# SDRAM.net
KiCad netlist of a schematic drawn in Altium Designer
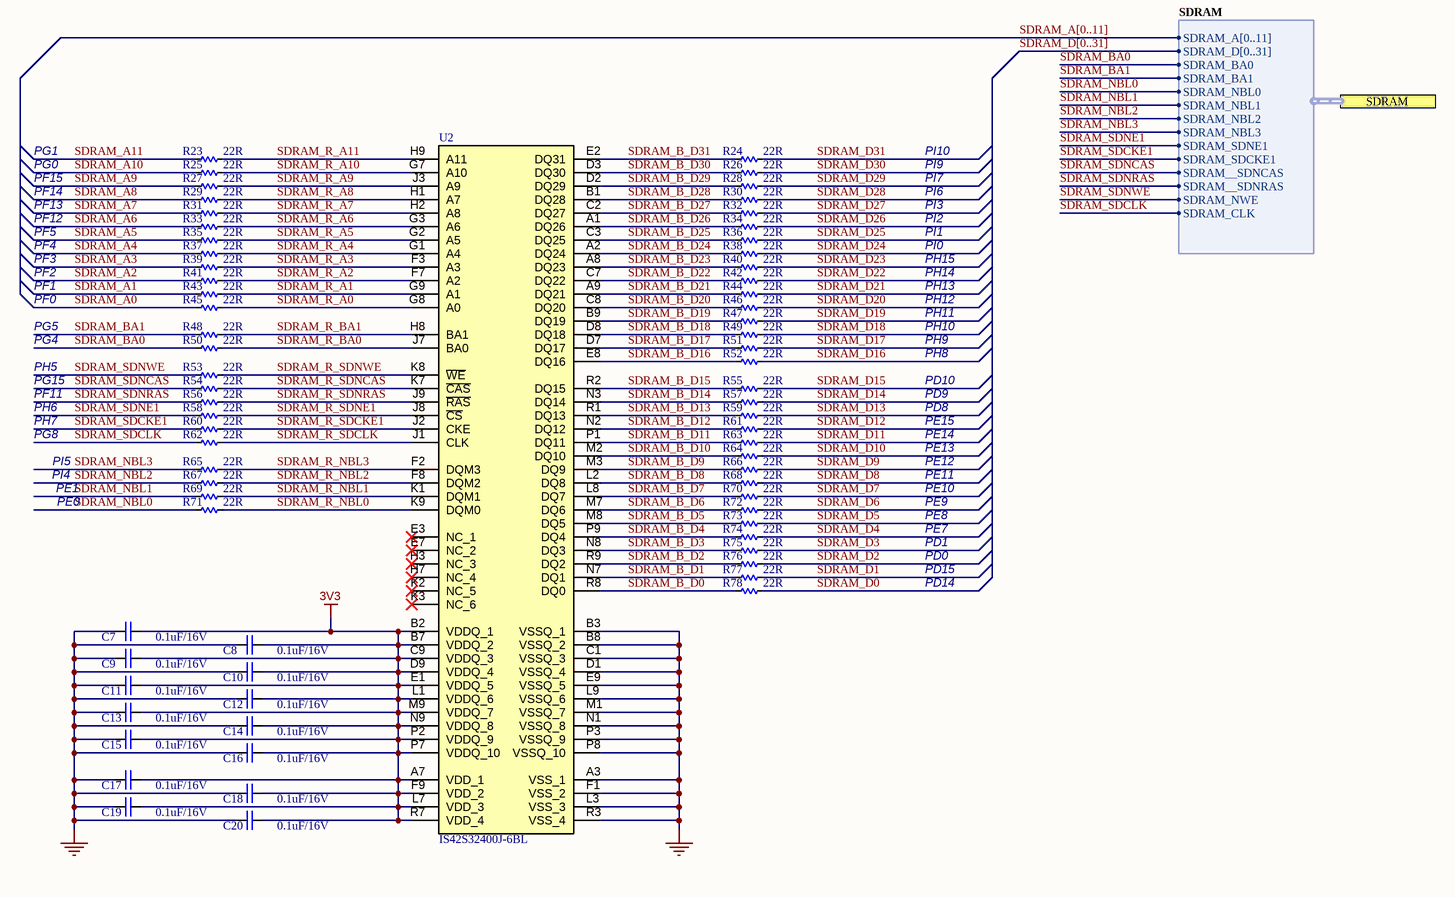
[diagram p0: SDRAM.SchDoc]

(export (version "E")
  (design (tool "Eeschema 10.0.6"))
  (components
    (comp (ref "C7")
      (value "0.1uF/16V")
      (footprint "CAP_C_1608X80")
      (description "CAP_Chip")
      (libsource (lib "LABLIB") (part "CAP_SMD"))
    )
    (comp (ref "C8")
      (value "0.1uF/16V")
      (footprint "CAP_C_1608X80")
      (description "CAP_Chip")
      (libsource (lib "LABLIB") (part "CAP_SMD"))
    )
    (comp (ref "C9")
      (value "0.1uF/16V")
      (footprint "CAP_C_1608X80")
      (description "CAP_Chip")
      (libsource (lib "LABLIB") (part "CAP_SMD"))
    )
    (comp (ref "C10")
      (value "0.1uF/16V")
      (footprint "CAP_C_1608X80")
      (description "CAP_Chip")
      (libsource (lib "LABLIB") (part "CAP_SMD"))
    )
    (comp (ref "C11")
      (value "0.1uF/16V")
      (footprint "CAP_C_1608X80")
      (description "CAP_Chip")
      (libsource (lib "LABLIB") (part "CAP_SMD"))
    )
    (comp (ref "C12")
      (value "0.1uF/16V")
      (footprint "CAP_C_1608X80")
      (description "CAP_Chip")
      (libsource (lib "LABLIB") (part "CAP_SMD"))
    )
    (comp (ref "C13")
      (value "0.1uF/16V")
      (footprint "CAP_C_1608X80")
      (description "CAP_Chip")
      (libsource (lib "LABLIB") (part "CAP_SMD"))
    )
    (comp (ref "C14")
      (value "0.1uF/16V")
      (footprint "CAP_C_1608X80")
      (description "CAP_Chip")
      (libsource (lib "LABLIB") (part "CAP_SMD"))
    )
    (comp (ref "C15")
      (value "0.1uF/16V")
      (footprint "CAP_C_1608X80")
      (description "CAP_Chip")
      (libsource (lib "LABLIB") (part "CAP_SMD"))
    )
    (comp (ref "C16")
      (value "0.1uF/16V")
      (footprint "CAP_C_1608X80")
      (description "CAP_Chip")
      (libsource (lib "LABLIB") (part "CAP_SMD"))
    )
    (comp (ref "C17")
      (value "0.1uF/16V")
      (footprint "CAP_C_1608X80")
      (description "CAP_Chip")
      (libsource (lib "LABLIB") (part "CAP_SMD"))
    )
    (comp (ref "C18")
      (value "0.1uF/16V")
      (footprint "CAP_C_1608X80")
      (description "CAP_Chip")
      (libsource (lib "LABLIB") (part "CAP_SMD"))
    )
    (comp (ref "C19")
      (value "0.1uF/16V")
      (footprint "CAP_C_1608X80")
      (description "CAP_Chip")
      (libsource (lib "LABLIB") (part "CAP_SMD"))
    )
    (comp (ref "C20")
      (value "0.1uF/16V")
      (footprint "CAP_C_1608X80")
      (description "CAP_Chip")
      (libsource (lib "LABLIB") (part "CAP_SMD"))
    )
    (comp (ref "R23")
      (value "22R")
      (footprint "RES_C_1608X60")
      (description "RES")
      (libsource (lib "LABLIB") (part "_RES_B_2"))
    )
    (comp (ref "R24")
      (value "22R")
      (footprint "RES_C_1608X60")
      (description "RES")
      (libsource (lib "LABLIB") (part "_RES_B_2"))
    )
    (comp (ref "R25")
      (value "22R")
      (footprint "RES_C_1608X60")
      (description "RES")
      (libsource (lib "LABLIB") (part "_RES_B_2"))
    )
    (comp (ref "R26")
      (value "22R")
      (footprint "RES_C_1608X60")
      (description "RES")
      (libsource (lib "LABLIB") (part "_RES_B_2"))
    )
    (comp (ref "R27")
      (value "22R")
      (footprint "RES_C_1608X60")
      (description "RES")
      (libsource (lib "LABLIB") (part "_RES_B_2"))
    )
    (comp (ref "R28")
      (value "22R")
      (footprint "RES_C_1608X60")
      (description "RES")
      (libsource (lib "LABLIB") (part "_RES_B_2"))
    )
    (comp (ref "R29")
      (value "22R")
      (footprint "RES_C_1608X60")
      (description "RES")
      (libsource (lib "LABLIB") (part "_RES_B_2"))
    )
    (comp (ref "R30")
      (value "22R")
      (footprint "RES_C_1608X60")
      (description "RES")
      (libsource (lib "LABLIB") (part "_RES_B_2"))
    )
    (comp (ref "R31")
      (value "22R")
      (footprint "RES_C_1608X60")
      (description "RES")
      (libsource (lib "LABLIB") (part "_RES_B_2"))
    )
    (comp (ref "R32")
      (value "22R")
      (footprint "RES_C_1608X60")
      (description "RES")
      (libsource (lib "LABLIB") (part "_RES_B_2"))
    )
    (comp (ref "R33")
      (value "22R")
      (footprint "RES_C_1608X60")
      (description "RES")
      (libsource (lib "LABLIB") (part "_RES_B_2"))
    )
    (comp (ref "R34")
      (value "22R")
      (footprint "RES_C_1608X60")
      (description "RES")
      (libsource (lib "LABLIB") (part "_RES_B_2"))
    )
    (comp (ref "R35")
      (value "22R")
      (footprint "RES_C_1608X60")
      (description "RES")
      (libsource (lib "LABLIB") (part "_RES_B_2"))
    )
    (comp (ref "R36")
      (value "22R")
      (footprint "RES_C_1608X60")
      (description "RES")
      (libsource (lib "LABLIB") (part "_RES_B_2"))
    )
    (comp (ref "R37")
      (value "22R")
      (footprint "RES_C_1608X60")
      (description "RES")
      (libsource (lib "LABLIB") (part "_RES_B_2"))
    )
    (comp (ref "R38")
      (value "22R")
      (footprint "RES_C_1608X60")
      (description "RES")
      (libsource (lib "LABLIB") (part "_RES_B_2"))
    )
    (comp (ref "R39")
      (value "22R")
      (footprint "RES_C_1608X60")
      (description "RES")
      (libsource (lib "LABLIB") (part "_RES_B_2"))
    )
    (comp (ref "R40")
      (value "22R")
      (footprint "RES_C_1608X60")
      (description "RES")
      (libsource (lib "LABLIB") (part "_RES_B_2"))
    )
    (comp (ref "R41")
      (value "22R")
      (footprint "RES_C_1608X60")
      (description "RES")
      (libsource (lib "LABLIB") (part "_RES_B_2"))
    )
    (comp (ref "R42")
      (value "22R")
      (footprint "RES_C_1608X60")
      (description "RES")
      (libsource (lib "LABLIB") (part "_RES_B_2"))
    )
    (comp (ref "R43")
      (value "22R")
      (footprint "RES_C_1608X60")
      (description "RES")
      (libsource (lib "LABLIB") (part "_RES_B_2"))
    )
    (comp (ref "R44")
      (value "22R")
      (footprint "RES_C_1608X60")
      (description "RES")
      (libsource (lib "LABLIB") (part "_RES_B_2"))
    )
    (comp (ref "R45")
      (value "22R")
      (footprint "RES_C_1608X60")
      (description "RES")
      (libsource (lib "LABLIB") (part "_RES_B_2"))
    )
    (comp (ref "R46")
      (value "22R")
      (footprint "RES_C_1608X60")
      (description "RES")
      (libsource (lib "LABLIB") (part "_RES_B_2"))
    )
    (comp (ref "R47")
      (value "22R")
      (footprint "RES_C_1608X60")
      (description "RES")
      (libsource (lib "LABLIB") (part "_RES_B_2"))
    )
    (comp (ref "R48")
      (value "22R")
      (footprint "RES_C_1608X60")
      (description "RES")
      (libsource (lib "LABLIB") (part "_RES_B_2"))
    )
    (comp (ref "R49")
      (value "22R")
      (footprint "RES_C_1608X60")
      (description "RES")
      (libsource (lib "LABLIB") (part "_RES_B_2"))
    )
    (comp (ref "R50")
      (value "22R")
      (footprint "RES_C_1608X60")
      (description "RES")
      (libsource (lib "LABLIB") (part "_RES_B_2"))
    )
    (comp (ref "R51")
      (value "22R")
      (footprint "RES_C_1608X60")
      (description "RES")
      (libsource (lib "LABLIB") (part "_RES_B_2"))
    )
    (comp (ref "R52")
      (value "22R")
      (footprint "RES_C_1608X60")
      (description "RES")
      (libsource (lib "LABLIB") (part "_RES_B_2"))
    )
    (comp (ref "R53")
      (value "22R")
      (footprint "RES_C_1608X60")
      (description "RES")
      (libsource (lib "LABLIB") (part "_RES_B_2"))
    )
    (comp (ref "R54")
      (value "22R")
      (footprint "RES_C_1608X60")
      (description "RES")
      (libsource (lib "LABLIB") (part "_RES_B_2"))
    )
    (comp (ref "R55")
      (value "22R")
      (footprint "RES_C_1608X60")
      (description "RES")
      (libsource (lib "LABLIB") (part "_RES_B_2"))
    )
    (comp (ref "R56")
      (value "22R")
      (footprint "RES_C_1608X60")
      (description "RES")
      (libsource (lib "LABLIB") (part "_RES_B_2"))
    )
    (comp (ref "R57")
      (value "22R")
      (footprint "RES_C_1608X60")
      (description "RES")
      (libsource (lib "LABLIB") (part "_RES_B_2"))
    )
    (comp (ref "R58")
      (value "22R")
      (footprint "RES_C_1608X60")
      (description "RES")
      (libsource (lib "LABLIB") (part "_RES_B_2"))
    )
    (comp (ref "R59")
      (value "22R")
      (footprint "RES_C_1608X60")
      (description "RES")
      (libsource (lib "LABLIB") (part "_RES_B_2"))
    )
    (comp (ref "R60")
      (value "22R")
      (footprint "RES_C_1608X60")
      (description "RES")
      (libsource (lib "LABLIB") (part "_RES_B_2"))
    )
    (comp (ref "R61")
      (value "22R")
      (footprint "RES_C_1608X60")
      (description "RES")
      (libsource (lib "LABLIB") (part "_RES_B_2"))
    )
    (comp (ref "R62")
      (value "22R")
      (footprint "RES_C_1608X60")
      (description "RES")
      (libsource (lib "LABLIB") (part "_RES_B_2"))
    )
    (comp (ref "R63")
      (value "22R")
      (footprint "RES_C_1608X60")
      (description "RES")
      (libsource (lib "LABLIB") (part "_RES_B_2"))
    )
    (comp (ref "R64")
      (value "22R")
      (footprint "RES_C_1608X60")
      (description "RES")
      (libsource (lib "LABLIB") (part "_RES_B_2"))
    )
    (comp (ref "R65")
      (value "22R")
      (footprint "RES_C_1608X60")
      (description "RES")
      (libsource (lib "LABLIB") (part "_RES_B_2"))
    )
    (comp (ref "R66")
      (value "22R")
      (footprint "RES_C_1608X60")
      (description "RES")
      (libsource (lib "LABLIB") (part "_RES_B_2"))
    )
    (comp (ref "R67")
      (value "22R")
      (footprint "RES_C_1608X60")
      (description "RES")
      (libsource (lib "LABLIB") (part "_RES_B_2"))
    )
    (comp (ref "R68")
      (value "22R")
      (footprint "RES_C_1608X60")
      (description "RES")
      (libsource (lib "LABLIB") (part "_RES_B_2"))
    )
    (comp (ref "R69")
      (value "22R")
      (footprint "RES_C_1608X60")
      (description "RES")
      (libsource (lib "LABLIB") (part "_RES_B_2"))
    )
    (comp (ref "R70")
      (value "22R")
      (footprint "RES_C_1608X60")
      (description "RES")
      (libsource (lib "LABLIB") (part "_RES_B_2"))
    )
    (comp (ref "R71")
      (value "22R")
      (footprint "RES_C_1608X60")
      (description "RES")
      (libsource (lib "LABLIB") (part "_RES_B_2"))
    )
    (comp (ref "R72")
      (value "22R")
      (footprint "RES_C_1608X60")
      (description "RES")
      (libsource (lib "LABLIB") (part "_RES_B_2"))
    )
    (comp (ref "R73")
      (value "22R")
      (footprint "RES_C_1608X60")
      (description "RES")
      (libsource (lib "LABLIB") (part "_RES_B_2"))
    )
    (comp (ref "R74")
      (value "22R")
      (footprint "RES_C_1608X60")
      (description "RES")
      (libsource (lib "LABLIB") (part "_RES_B_2"))
    )
    (comp (ref "R75")
      (value "22R")
      (footprint "RES_C_1608X60")
      (description "RES")
      (libsource (lib "LABLIB") (part "_RES_B_2"))
    )
    (comp (ref "R76")
      (value "22R")
      (footprint "RES_C_1608X60")
      (description "RES")
      (libsource (lib "LABLIB") (part "_RES_B_2"))
    )
    (comp (ref "R77")
      (value "22R")
      (footprint "RES_C_1608X60")
      (description "RES")
      (libsource (lib "LABLIB") (part "_RES_B_2"))
    )
    (comp (ref "R78")
      (value "22R")
      (footprint "RES_C_1608X60")
      (description "RES")
      (libsource (lib "LABLIB") (part "_RES_B_2"))
    )
    (comp (ref "U2")
      (value "IS42S32400J-6BL")
      (footprint "BGA90C80P9X15_800X1300X120")
      (description "DRAM 128M, 3.3V, SDRAM, 4Mx32, 166Mhz, 90 ball BGA (8mmx13mm) RoHS")
      (libsource (lib "COMM_SCHLIB") (part "IS42S32400J-6BL"))
    )
  )
  (nets
    (net (code "2") (name "/SDRAM_A0") (class "Default")
      (node (ref "R45") (pin "1") (pinfunction "1_1") (pintype "passive"))
    )
    (net (code "3") (name "/SDRAM_A1") (class "Default")
      (node (ref "R43") (pin "1") (pinfunction "1_1") (pintype "passive"))
    )
    (net (code "4") (name "/SDRAM_A2") (class "Default")
      (node (ref "R41") (pin "1") (pinfunction "1_1") (pintype "passive"))
    )
    (net (code "5") (name "/SDRAM_A3") (class "Default")
      (node (ref "R39") (pin "1") (pinfunction "1_1") (pintype "passive"))
    )
    (net (code "6") (name "/SDRAM_A4") (class "Default")
      (node (ref "R37") (pin "1") (pinfunction "1_1") (pintype "passive"))
    )
    (net (code "7") (name "/SDRAM_A5") (class "Default")
      (node (ref "R35") (pin "1") (pinfunction "1_1") (pintype "passive"))
    )
    (net (code "8") (name "/SDRAM_A6") (class "Default")
      (node (ref "R33") (pin "1") (pinfunction "1_1") (pintype "passive"))
    )
    (net (code "9") (name "/SDRAM_A7") (class "Default")
      (node (ref "R31") (pin "1") (pinfunction "1_1") (pintype "passive"))
    )
    (net (code "10") (name "/SDRAM_A8") (class "Default")
      (node (ref "R29") (pin "1") (pinfunction "1_1") (pintype "passive"))
    )
    (net (code "11") (name "/SDRAM_A9") (class "Default")
      (node (ref "R27") (pin "1") (pinfunction "1_1") (pintype "passive"))
    )
    (net (code "12") (name "/SDRAM_A10") (class "Default")
      (node (ref "R25") (pin "1") (pinfunction "1_1") (pintype "passive"))
    )
    (net (code "13") (name "/SDRAM_A11") (class "Default")
      (node (ref "R23") (pin "1") (pinfunction "1_1") (pintype "passive"))
    )
    (net (code "15") (name "/SDRAM_BA0") (class "Default")
      (node (ref "R50") (pin "1") (pinfunction "1_1") (pintype "passive"))
    )
    (net (code "16") (name "/SDRAM_BA1") (class "Default")
      (node (ref "R48") (pin "1") (pinfunction "1_1") (pintype "passive"))
    )
    (net (code "17") (name "/SDRAM_B_D0") (class "Default")
      (node (ref "R78") (pin "1") (pinfunction "1_1") (pintype "passive"))
      (node (ref "U2") (pin "R8") (pinfunction "DQ0_R8") (pintype "passive"))
    )
    (net (code "18") (name "/SDRAM_B_D1") (class "Default")
      (node (ref "R77") (pin "1") (pinfunction "1_1") (pintype "passive"))
      (node (ref "U2") (pin "N7") (pinfunction "DQ1_N7") (pintype "passive"))
    )
    (net (code "19") (name "/SDRAM_B_D2") (class "Default")
      (node (ref "R76") (pin "1") (pinfunction "1_1") (pintype "passive"))
      (node (ref "U2") (pin "R9") (pinfunction "DQ2_R9") (pintype "passive"))
    )
    (net (code "20") (name "/SDRAM_B_D3") (class "Default")
      (node (ref "R75") (pin "1") (pinfunction "1_1") (pintype "passive"))
      (node (ref "U2") (pin "N8") (pinfunction "DQ3_N8") (pintype "passive"))
    )
    (net (code "21") (name "/SDRAM_B_D4") (class "Default")
      (node (ref "R74") (pin "1") (pinfunction "1_1") (pintype "passive"))
      (node (ref "U2") (pin "P9") (pinfunction "DQ4_P9") (pintype "passive"))
    )
    (net (code "22") (name "/SDRAM_B_D5") (class "Default")
      (node (ref "R73") (pin "1") (pinfunction "1_1") (pintype "passive"))
      (node (ref "U2") (pin "M8") (pinfunction "DQ5_M8") (pintype "passive"))
    )
    (net (code "23") (name "/SDRAM_B_D6") (class "Default")
      (node (ref "R72") (pin "1") (pinfunction "1_1") (pintype "passive"))
      (node (ref "U2") (pin "M7") (pinfunction "DQ6_M7") (pintype "passive"))
    )
    (net (code "24") (name "/SDRAM_B_D7") (class "Default")
      (node (ref "R70") (pin "1") (pinfunction "1_1") (pintype "passive"))
      (node (ref "U2") (pin "L8") (pinfunction "DQ7_L8") (pintype "passive"))
    )
    (net (code "25") (name "/SDRAM_B_D8") (class "Default")
      (node (ref "R68") (pin "1") (pinfunction "1_1") (pintype "passive"))
      (node (ref "U2") (pin "L2") (pinfunction "DQ8_L2") (pintype "passive"))
    )
    (net (code "26") (name "/SDRAM_B_D9") (class "Default")
      (node (ref "R66") (pin "1") (pinfunction "1_1") (pintype "passive"))
      (node (ref "U2") (pin "M3") (pinfunction "DQ9_M3") (pintype "passive"))
    )
    (net (code "27") (name "/SDRAM_B_D10") (class "Default")
      (node (ref "R64") (pin "1") (pinfunction "1_1") (pintype "passive"))
      (node (ref "U2") (pin "M2") (pinfunction "DQ10_M2") (pintype "passive"))
    )
    (net (code "28") (name "/SDRAM_B_D11") (class "Default")
      (node (ref "R63") (pin "1") (pinfunction "1_1") (pintype "passive"))
      (node (ref "U2") (pin "P1") (pinfunction "DQ11_P1") (pintype "passive"))
    )
    (net (code "29") (name "/SDRAM_B_D12") (class "Default")
      (node (ref "R61") (pin "1") (pinfunction "1_1") (pintype "passive"))
      (node (ref "U2") (pin "N2") (pinfunction "DQ12_N2") (pintype "passive"))
    )
    (net (code "30") (name "/SDRAM_B_D13") (class "Default")
      (node (ref "R59") (pin "1") (pinfunction "1_1") (pintype "passive"))
      (node (ref "U2") (pin "R1") (pinfunction "DQ13_R1") (pintype "passive"))
    )
    (net (code "31") (name "/SDRAM_B_D14") (class "Default")
      (node (ref "R57") (pin "1") (pinfunction "1_1") (pintype "passive"))
      (node (ref "U2") (pin "N3") (pinfunction "DQ14_N3") (pintype "passive"))
    )
    (net (code "32") (name "/SDRAM_B_D15") (class "Default")
      (node (ref "R55") (pin "1") (pinfunction "1_1") (pintype "passive"))
      (node (ref "U2") (pin "R2") (pinfunction "DQ15_R2") (pintype "passive"))
    )
    (net (code "33") (name "/SDRAM_B_D16") (class "Default")
      (node (ref "R52") (pin "1") (pinfunction "1_1") (pintype "passive"))
      (node (ref "U2") (pin "E8") (pinfunction "DQ16_E8") (pintype "passive"))
    )
    (net (code "34") (name "/SDRAM_B_D17") (class "Default")
      (node (ref "R51") (pin "1") (pinfunction "1_1") (pintype "passive"))
      (node (ref "U2") (pin "D7") (pinfunction "DQ17_D7") (pintype "passive"))
    )
    (net (code "35") (name "/SDRAM_B_D18") (class "Default")
      (node (ref "R49") (pin "1") (pinfunction "1_1") (pintype "passive"))
      (node (ref "U2") (pin "D8") (pinfunction "DQ18_D8") (pintype "passive"))
    )
    (net (code "36") (name "/SDRAM_B_D19") (class "Default")
      (node (ref "R47") (pin "1") (pinfunction "1_1") (pintype "passive"))
      (node (ref "U2") (pin "B9") (pinfunction "DQ19_B9") (pintype "passive"))
    )
    (net (code "37") (name "/SDRAM_B_D20") (class "Default")
      (node (ref "R46") (pin "1") (pinfunction "1_1") (pintype "passive"))
      (node (ref "U2") (pin "C8") (pinfunction "DQ20_C8") (pintype "passive"))
    )
    (net (code "38") (name "/SDRAM_B_D21") (class "Default")
      (node (ref "R44") (pin "1") (pinfunction "1_1") (pintype "passive"))
      (node (ref "U2") (pin "A9") (pinfunction "DQ21_A9") (pintype "passive"))
    )
    (net (code "39") (name "/SDRAM_B_D22") (class "Default")
      (node (ref "R42") (pin "1") (pinfunction "1_1") (pintype "passive"))
      (node (ref "U2") (pin "C7") (pinfunction "DQ22_C7") (pintype "passive"))
    )
    (net (code "40") (name "/SDRAM_B_D23") (class "Default")
      (node (ref "R40") (pin "1") (pinfunction "1_1") (pintype "passive"))
      (node (ref "U2") (pin "A8") (pinfunction "DQ23_A8") (pintype "passive"))
    )
    (net (code "41") (name "/SDRAM_B_D24") (class "Default")
      (node (ref "R38") (pin "1") (pinfunction "1_1") (pintype "passive"))
      (node (ref "U2") (pin "A2") (pinfunction "DQ24_A2") (pintype "passive"))
    )
    (net (code "42") (name "/SDRAM_B_D25") (class "Default")
      (node (ref "R36") (pin "1") (pinfunction "1_1") (pintype "passive"))
      (node (ref "U2") (pin "C3") (pinfunction "DQ25_C3") (pintype "passive"))
    )
    (net (code "43") (name "/SDRAM_B_D26") (class "Default")
      (node (ref "R34") (pin "1") (pinfunction "1_1") (pintype "passive"))
      (node (ref "U2") (pin "A1") (pinfunction "DQ26_A1") (pintype "passive"))
    )
    (net (code "44") (name "/SDRAM_B_D27") (class "Default")
      (node (ref "R32") (pin "1") (pinfunction "1_1") (pintype "passive"))
      (node (ref "U2") (pin "C2") (pinfunction "DQ27_C2") (pintype "passive"))
    )
    (net (code "45") (name "/SDRAM_B_D28") (class "Default")
      (node (ref "R30") (pin "1") (pinfunction "1_1") (pintype "passive"))
      (node (ref "U2") (pin "B1") (pinfunction "DQ28_B1") (pintype "passive"))
    )
    (net (code "46") (name "/SDRAM_B_D29") (class "Default")
      (node (ref "R28") (pin "1") (pinfunction "1_1") (pintype "passive"))
      (node (ref "U2") (pin "D2") (pinfunction "DQ29_D2") (pintype "passive"))
    )
    (net (code "47") (name "/SDRAM_B_D30") (class "Default")
      (node (ref "R26") (pin "1") (pinfunction "1_1") (pintype "passive"))
      (node (ref "U2") (pin "D3") (pinfunction "DQ30_D3") (pintype "passive"))
    )
    (net (code "48") (name "/SDRAM_B_D31") (class "Default")
      (node (ref "R24") (pin "1") (pinfunction "1_1") (pintype "passive"))
      (node (ref "U2") (pin "E2") (pinfunction "DQ31_E2") (pintype "passive"))
    )
    (net (code "49") (name "/SDRAM_D0") (class "Default")
      (node (ref "R78") (pin "2") (pinfunction "2_2") (pintype "passive"))
    )
    (net (code "50") (name "/SDRAM_D1") (class "Default")
      (node (ref "R77") (pin "2") (pinfunction "2_2") (pintype "passive"))
    )
    (net (code "51") (name "/SDRAM_D2") (class "Default")
      (node (ref "R76") (pin "2") (pinfunction "2_2") (pintype "passive"))
    )
    (net (code "52") (name "/SDRAM_D3") (class "Default")
      (node (ref "R75") (pin "2") (pinfunction "2_2") (pintype "passive"))
    )
    (net (code "53") (name "/SDRAM_D4") (class "Default")
      (node (ref "R74") (pin "2") (pinfunction "2_2") (pintype "passive"))
    )
    (net (code "54") (name "/SDRAM_D5") (class "Default")
      (node (ref "R73") (pin "2") (pinfunction "2_2") (pintype "passive"))
    )
    (net (code "55") (name "/SDRAM_D6") (class "Default")
      (node (ref "R72") (pin "2") (pinfunction "2_2") (pintype "passive"))
    )
    (net (code "56") (name "/SDRAM_D7") (class "Default")
      (node (ref "R70") (pin "2") (pinfunction "2_2") (pintype "passive"))
    )
    (net (code "57") (name "/SDRAM_D8") (class "Default")
      (node (ref "R68") (pin "2") (pinfunction "2_2") (pintype "passive"))
    )
    (net (code "58") (name "/SDRAM_D9") (class "Default")
      (node (ref "R66") (pin "2") (pinfunction "2_2") (pintype "passive"))
    )
    (net (code "59") (name "/SDRAM_D10") (class "Default")
      (node (ref "R64") (pin "2") (pinfunction "2_2") (pintype "passive"))
    )
    (net (code "60") (name "/SDRAM_D11") (class "Default")
      (node (ref "R63") (pin "2") (pinfunction "2_2") (pintype "passive"))
    )
    (net (code "61") (name "/SDRAM_D12") (class "Default")
      (node (ref "R61") (pin "2") (pinfunction "2_2") (pintype "passive"))
    )
    (net (code "62") (name "/SDRAM_D13") (class "Default")
      (node (ref "R59") (pin "2") (pinfunction "2_2") (pintype "passive"))
    )
    (net (code "63") (name "/SDRAM_D14") (class "Default")
      (node (ref "R57") (pin "2") (pinfunction "2_2") (pintype "passive"))
    )
    (net (code "64") (name "/SDRAM_D15") (class "Default")
      (node (ref "R55") (pin "2") (pinfunction "2_2") (pintype "passive"))
    )
    (net (code "65") (name "/SDRAM_D16") (class "Default")
      (node (ref "R52") (pin "2") (pinfunction "2_2") (pintype "passive"))
    )
    (net (code "66") (name "/SDRAM_D17") (class "Default")
      (node (ref "R51") (pin "2") (pinfunction "2_2") (pintype "passive"))
    )
    (net (code "67") (name "/SDRAM_D18") (class "Default")
      (node (ref "R49") (pin "2") (pinfunction "2_2") (pintype "passive"))
    )
    (net (code "68") (name "/SDRAM_D19") (class "Default")
      (node (ref "R47") (pin "2") (pinfunction "2_2") (pintype "passive"))
    )
    (net (code "69") (name "/SDRAM_D20") (class "Default")
      (node (ref "R46") (pin "2") (pinfunction "2_2") (pintype "passive"))
    )
    (net (code "70") (name "/SDRAM_D21") (class "Default")
      (node (ref "R44") (pin "2") (pinfunction "2_2") (pintype "passive"))
    )
    (net (code "71") (name "/SDRAM_D22") (class "Default")
      (node (ref "R42") (pin "2") (pinfunction "2_2") (pintype "passive"))
    )
    (net (code "72") (name "/SDRAM_D23") (class "Default")
      (node (ref "R40") (pin "2") (pinfunction "2_2") (pintype "passive"))
    )
    (net (code "73") (name "/SDRAM_D24") (class "Default")
      (node (ref "R38") (pin "2") (pinfunction "2_2") (pintype "passive"))
    )
    (net (code "74") (name "/SDRAM_D25") (class "Default")
      (node (ref "R36") (pin "2") (pinfunction "2_2") (pintype "passive"))
    )
    (net (code "75") (name "/SDRAM_D26") (class "Default")
      (node (ref "R34") (pin "2") (pinfunction "2_2") (pintype "passive"))
    )
    (net (code "76") (name "/SDRAM_D27") (class "Default")
      (node (ref "R32") (pin "2") (pinfunction "2_2") (pintype "passive"))
    )
    (net (code "77") (name "/SDRAM_D28") (class "Default")
      (node (ref "R30") (pin "2") (pinfunction "2_2") (pintype "passive"))
    )
    (net (code "78") (name "/SDRAM_D29") (class "Default")
      (node (ref "R28") (pin "2") (pinfunction "2_2") (pintype "passive"))
    )
    (net (code "79") (name "/SDRAM_D30") (class "Default")
      (node (ref "R26") (pin "2") (pinfunction "2_2") (pintype "passive"))
    )
    (net (code "80") (name "/SDRAM_D31") (class "Default")
      (node (ref "R24") (pin "2") (pinfunction "2_2") (pintype "passive"))
    )
    (net (code "82") (name "/SDRAM_NBL0") (class "Default")
      (node (ref "R71") (pin "1") (pinfunction "1_1") (pintype "passive"))
    )
    (net (code "83") (name "/SDRAM_NBL1") (class "Default")
      (node (ref "R69") (pin "1") (pinfunction "1_1") (pintype "passive"))
    )
    (net (code "84") (name "/SDRAM_NBL2") (class "Default")
      (node (ref "R67") (pin "1") (pinfunction "1_1") (pintype "passive"))
    )
    (net (code "85") (name "/SDRAM_NBL3") (class "Default")
      (node (ref "R65") (pin "1") (pinfunction "1_1") (pintype "passive"))
    )
    (net (code "86") (name "/SDRAM_R_A0") (class "Default")
      (node (ref "R45") (pin "2") (pinfunction "2_2") (pintype "passive"))
      (node (ref "U2") (pin "G8") (pinfunction "A0_G8") (pintype "passive"))
    )
    (net (code "87") (name "/SDRAM_R_A1") (class "Default")
      (node (ref "R43") (pin "2") (pinfunction "2_2") (pintype "passive"))
      (node (ref "U2") (pin "G9") (pinfunction "A1_G9") (pintype "passive"))
    )
    (net (code "88") (name "/SDRAM_R_A2") (class "Default")
      (node (ref "R41") (pin "2") (pinfunction "2_2") (pintype "passive"))
      (node (ref "U2") (pin "F7") (pinfunction "A2_F7") (pintype "passive"))
    )
    (net (code "89") (name "/SDRAM_R_A3") (class "Default")
      (node (ref "R39") (pin "2") (pinfunction "2_2") (pintype "passive"))
      (node (ref "U2") (pin "F3") (pinfunction "A3_F3") (pintype "passive"))
    )
    (net (code "90") (name "/SDRAM_R_A4") (class "Default")
      (node (ref "R37") (pin "2") (pinfunction "2_2") (pintype "passive"))
      (node (ref "U2") (pin "G1") (pinfunction "A4_G1") (pintype "passive"))
    )
    (net (code "91") (name "/SDRAM_R_A5") (class "Default")
      (node (ref "R35") (pin "2") (pinfunction "2_2") (pintype "passive"))
      (node (ref "U2") (pin "G2") (pinfunction "A5_G2") (pintype "passive"))
    )
    (net (code "92") (name "/SDRAM_R_A6") (class "Default")
      (node (ref "R33") (pin "2") (pinfunction "2_2") (pintype "passive"))
      (node (ref "U2") (pin "G3") (pinfunction "A6_G3") (pintype "passive"))
    )
    (net (code "93") (name "/SDRAM_R_A7") (class "Default")
      (node (ref "R31") (pin "2") (pinfunction "2_2") (pintype "passive"))
      (node (ref "U2") (pin "H2") (pinfunction "A8_H2") (pintype "passive"))
    )
    (net (code "94") (name "/SDRAM_R_A8") (class "Default")
      (node (ref "R29") (pin "2") (pinfunction "2_2") (pintype "passive"))
      (node (ref "U2") (pin "H1") (pinfunction "A7_H1") (pintype "passive"))
    )
    (net (code "95") (name "/SDRAM_R_A9") (class "Default")
      (node (ref "R27") (pin "2") (pinfunction "2_2") (pintype "passive"))
      (node (ref "U2") (pin "J3") (pinfunction "A9_J3") (pintype "passive"))
    )
    (net (code "96") (name "/SDRAM_R_A10") (class "Default")
      (node (ref "R25") (pin "2") (pinfunction "2_2") (pintype "passive"))
      (node (ref "U2") (pin "G7") (pinfunction "A10_G7") (pintype "passive"))
    )
    (net (code "97") (name "/SDRAM_R_A11") (class "Default")
      (node (ref "R23") (pin "2") (pinfunction "2_2") (pintype "passive"))
      (node (ref "U2") (pin "H9") (pinfunction "A11_H9") (pintype "passive"))
    )
    (net (code "98") (name "/SDRAM_R_BA0") (class "Default")
      (node (ref "R50") (pin "2") (pinfunction "2_2") (pintype "passive"))
      (node (ref "U2") (pin "J7") (pinfunction "BA0_J7") (pintype "passive"))
    )
    (net (code "99") (name "/SDRAM_R_BA1") (class "Default")
      (node (ref "R48") (pin "2") (pinfunction "2_2") (pintype "passive"))
      (node (ref "U2") (pin "H8") (pinfunction "BA1_H8") (pintype "passive"))
    )
    (net (code "100") (name "/SDRAM_R_NBL0") (class "Default")
      (node (ref "R71") (pin "2") (pinfunction "2_2") (pintype "passive"))
      (node (ref "U2") (pin "K9") (pinfunction "DQM0_K9") (pintype "passive"))
    )
    (net (code "101") (name "/SDRAM_R_NBL1") (class "Default")
      (node (ref "R69") (pin "2") (pinfunction "2_2") (pintype "passive"))
      (node (ref "U2") (pin "K1") (pinfunction "DQM1_K1") (pintype "passive"))
    )
    (net (code "102") (name "/SDRAM_R_NBL2") (class "Default")
      (node (ref "R67") (pin "2") (pinfunction "2_2") (pintype "passive"))
      (node (ref "U2") (pin "F8") (pinfunction "DQM2_F8") (pintype "passive"))
    )
    (net (code "103") (name "/SDRAM_R_NBL3") (class "Default")
      (node (ref "R65") (pin "2") (pinfunction "2_2") (pintype "passive"))
      (node (ref "U2") (pin "F2") (pinfunction "DQM3_F2") (pintype "passive"))
    )
    (net (code "104") (name "/SDRAM_R_SDCKE1") (class "Default")
      (node (ref "R60") (pin "2") (pinfunction "2_2") (pintype "passive"))
      (node (ref "U2") (pin "J2") (pinfunction "CKE_J2") (pintype "passive"))
    )
    (net (code "105") (name "/SDRAM_R_SDCLK") (class "Default")
      (node (ref "R62") (pin "2") (pinfunction "2_2") (pintype "passive"))
      (node (ref "U2") (pin "J1") (pinfunction "CLK_J1") (pintype "passive"))
    )
    (net (code "106") (name "/SDRAM_R_SDNCAS") (class "Default")
      (node (ref "R54") (pin "2") (pinfunction "2_2") (pintype "passive"))
      (node (ref "U2") (pin "K7") (pinfunction "~{CAS}_K7") (pintype "passive"))
    )
    (net (code "107") (name "/SDRAM_R_SDNE1") (class "Default")
      (node (ref "R58") (pin "2") (pinfunction "2_2") (pintype "passive"))
      (node (ref "U2") (pin "J8") (pinfunction "~{CS}_J8") (pintype "passive"))
    )
    (net (code "108") (name "/SDRAM_R_SDNRAS") (class "Default")
      (node (ref "R56") (pin "2") (pinfunction "2_2") (pintype "passive"))
      (node (ref "U2") (pin "J9") (pinfunction "~{RAS}_J9") (pintype "passive"))
    )
    (net (code "109") (name "/SDRAM_R_SDNWE") (class "Default")
      (node (ref "R53") (pin "2") (pinfunction "2_2") (pintype "passive"))
      (node (ref "U2") (pin "K8") (pinfunction "~{WE}_K8") (pintype "passive"))
    )
    (net (code "110") (name "/SDRAM_SDCKE1") (class "Default")
      (node (ref "R60") (pin "1") (pinfunction "1_1") (pintype "passive"))
    )
    (net (code "111") (name "/SDRAM_SDCLK") (class "Default")
      (node (ref "R62") (pin "1") (pinfunction "1_1") (pintype "passive"))
    )
    (net (code "112") (name "/SDRAM_SDNCAS") (class "Default")
      (node (ref "R54") (pin "1") (pinfunction "1_1") (pintype "passive"))
    )
    (net (code "113") (name "/SDRAM_SDNE1") (class "Default")
      (node (ref "R58") (pin "1") (pinfunction "1_1") (pintype "passive"))
    )
    (net (code "114") (name "/SDRAM_SDNRAS") (class "Default")
      (node (ref "R56") (pin "1") (pinfunction "1_1") (pintype "passive"))
    )
    (net (code "115") (name "/SDRAM_SDNWE") (class "Default")
      (node (ref "R53") (pin "1") (pinfunction "1_1") (pintype "passive"))
    )
    (net (code "117") (name "3V3") (class "Default")
      (node (ref "C10") (pin "2") (pinfunction "2_2") (pintype "passive"))
      (node (ref "C11") (pin "2") (pinfunction "2_2") (pintype "passive"))
      (node (ref "C12") (pin "2") (pinfunction "2_2") (pintype "passive"))
      (node (ref "C13") (pin "2") (pinfunction "2_2") (pintype "passive"))
      (node (ref "C14") (pin "2") (pinfunction "2_2") (pintype "passive"))
      (node (ref "C15") (pin "2") (pinfunction "2_2") (pintype "passive"))
      (node (ref "C16") (pin "2") (pinfunction "2_2") (pintype "passive"))
      (node (ref "C17") (pin "2") (pinfunction "2_2") (pintype "passive"))
      (node (ref "C18") (pin "2") (pinfunction "2_2") (pintype "passive"))
      (node (ref "C19") (pin "2") (pinfunction "2_2") (pintype "passive"))
      (node (ref "C20") (pin "2") (pinfunction "2_2") (pintype "passive"))
      (node (ref "C7") (pin "2") (pinfunction "2_2") (pintype "passive"))
      (node (ref "C8") (pin "2") (pinfunction "2_2") (pintype "passive"))
      (node (ref "C9") (pin "2") (pinfunction "2_2") (pintype "passive"))
      (node (ref "U2") (pin "A7") (pinfunction "VDD_1_A7") (pintype "passive"))
      (node (ref "U2") (pin "B2") (pinfunction "VDDQ_1_B2") (pintype "passive"))
      (node (ref "U2") (pin "B7") (pinfunction "VDDQ_2_B7") (pintype "passive"))
      (node (ref "U2") (pin "C9") (pinfunction "VDDQ_3_C9") (pintype "passive"))
      (node (ref "U2") (pin "D9") (pinfunction "VDDQ_4_D9") (pintype "passive"))
      (node (ref "U2") (pin "E1") (pinfunction "VDDQ_5_E1") (pintype "passive"))
      (node (ref "U2") (pin "F9") (pinfunction "VDD_2_F9") (pintype "passive"))
      (node (ref "U2") (pin "L1") (pinfunction "VDDQ_6_L1") (pintype "passive"))
      (node (ref "U2") (pin "L7") (pinfunction "VDD_3_L7") (pintype "passive"))
      (node (ref "U2") (pin "M9") (pinfunction "VDDQ_7_M9") (pintype "passive"))
      (node (ref "U2") (pin "N9") (pinfunction "VDDQ_8_N9") (pintype "passive"))
      (node (ref "U2") (pin "P2") (pinfunction "VDDQ_9_P2") (pintype "passive"))
      (node (ref "U2") (pin "P7") (pinfunction "VDDQ_10_P7") (pintype "passive"))
      (node (ref "U2") (pin "R7") (pinfunction "VDD_4_R7") (pintype "passive"))
    )
    (net (code "118") (name "GND") (class "Default")
      (node (ref "C10") (pin "1") (pinfunction "1_1") (pintype "passive"))
      (node (ref "C11") (pin "1") (pinfunction "1_1") (pintype "passive"))
      (node (ref "C12") (pin "1") (pinfunction "1_1") (pintype "passive"))
      (node (ref "C13") (pin "1") (pinfunction "1_1") (pintype "passive"))
      (node (ref "C14") (pin "1") (pinfunction "1_1") (pintype "passive"))
      (node (ref "C15") (pin "1") (pinfunction "1_1") (pintype "passive"))
      (node (ref "C16") (pin "1") (pinfunction "1_1") (pintype "passive"))
      (node (ref "C17") (pin "1") (pinfunction "1_1") (pintype "passive"))
      (node (ref "C18") (pin "1") (pinfunction "1_1") (pintype "passive"))
      (node (ref "C19") (pin "1") (pinfunction "1_1") (pintype "passive"))
      (node (ref "C20") (pin "1") (pinfunction "1_1") (pintype "passive"))
      (node (ref "C7") (pin "1") (pinfunction "1_1") (pintype "passive"))
      (node (ref "C8") (pin "1") (pinfunction "1_1") (pintype "passive"))
      (node (ref "C9") (pin "1") (pinfunction "1_1") (pintype "passive"))
      (node (ref "U2") (pin "A3") (pinfunction "VSS_1_A3") (pintype "passive"))
      (node (ref "U2") (pin "B3") (pinfunction "VSSQ_1_B3") (pintype "passive"))
      (node (ref "U2") (pin "B8") (pinfunction "VSSQ_2_B8") (pintype "passive"))
      (node (ref "U2") (pin "C1") (pinfunction "VSSQ_3_C1") (pintype "passive"))
      (node (ref "U2") (pin "D1") (pinfunction "VSSQ_4_D1") (pintype "passive"))
      (node (ref "U2") (pin "E9") (pinfunction "VSSQ_5_E9") (pintype "passive"))
      (node (ref "U2") (pin "F1") (pinfunction "VSS_2_F1") (pintype "passive"))
      (node (ref "U2") (pin "L3") (pinfunction "VSS_3_L3") (pintype "passive"))
      (node (ref "U2") (pin "L9") (pinfunction "VSSQ_6_L9") (pintype "passive"))
      (node (ref "U2") (pin "M1") (pinfunction "VSSQ_7_M1") (pintype "passive"))
      (node (ref "U2") (pin "N1") (pinfunction "VSSQ_8_N1") (pintype "passive"))
      (node (ref "U2") (pin "P3") (pinfunction "VSSQ_9_P3") (pintype "passive"))
      (node (ref "U2") (pin "P8") (pinfunction "VSSQ_10_P8") (pintype "passive"))
      (node (ref "U2") (pin "R3") (pinfunction "VSS_4_R3") (pintype "passive"))
    )
    (net (code "119") (name "unconnected-(U2-NC_1-PadE3)") (class "Default")
      (node (ref "U2") (pin "E3") (pinfunction "NC_1_E3") (pintype "passive+no_connect"))
    )
    (net (code "120") (name "unconnected-(U2-NC_2-PadE7)") (class "Default")
      (node (ref "U2") (pin "E7") (pinfunction "NC_2_E7") (pintype "passive+no_connect"))
    )
    (net (code "121") (name "unconnected-(U2-NC_3-PadH3)") (class "Default")
      (node (ref "U2") (pin "H3") (pinfunction "NC_3_H3") (pintype "passive+no_connect"))
    )
    (net (code "122") (name "unconnected-(U2-NC_4-PadH7)") (class "Default")
      (node (ref "U2") (pin "H7") (pinfunction "NC_4_H7") (pintype "passive+no_connect"))
    )
    (net (code "123") (name "unconnected-(U2-NC_5-PadK2)") (class "Default")
      (node (ref "U2") (pin "K2") (pinfunction "NC_5_K2") (pintype "passive+no_connect"))
    )
    (net (code "124") (name "unconnected-(U2-NC_6-PadK3)") (class "Default")
      (node (ref "U2") (pin "K3") (pinfunction "NC_6_K3") (pintype "passive+no_connect"))
    )
  )
)
